# common-collector.net
KiCad netlist of a schematic drawn in EAGLE
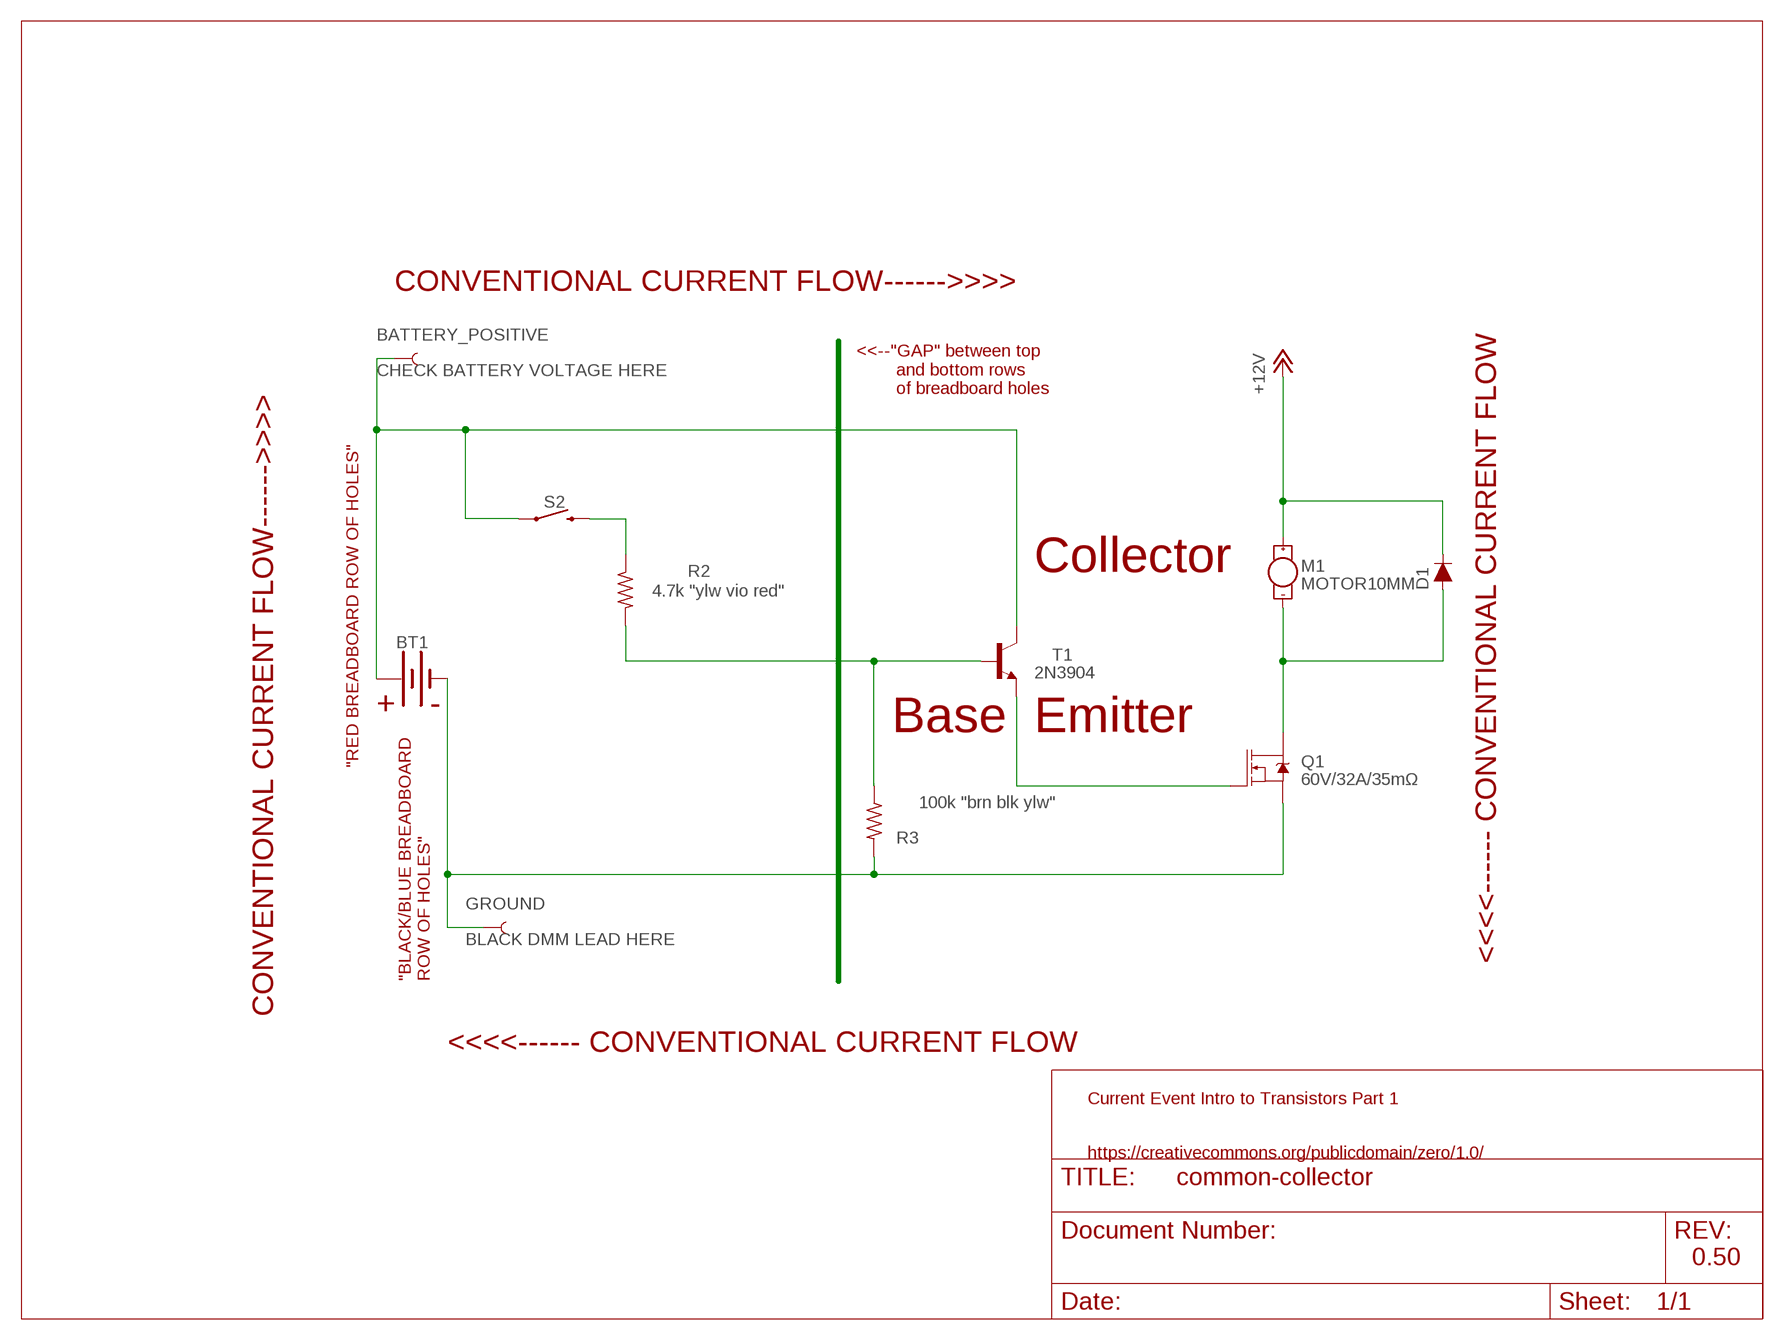
[diagram p0: schematic, sheet 1]

(export (version "E")
  (design (tool "Eeschema 10.0.6"))
  (components
    (comp (ref "BATTERY_POSITIVE")
      (value "CHECK BATTERY VOLTAGE HERE")
      (footprint "eagle-import:PAD.02X.02")
      (libsource (lib "eagle-import") (part "TEST-POINT2"))
    )
    (comp (ref "BT1")
      (value "BATTERY-AAA_KIT")
      (footprint "eagle-import:BATTERY-AAA-KIT")
      (libsource (lib "eagle-import") (part "BATTERY-AAA_KIT"))
    )
    (comp (ref "D1")
      (value "DIODE-1N4148")
      (footprint "eagle-import:DIODE-1N4148")
      (libsource (lib "eagle-import") (part "DIODE-1N4148"))
    )
    (comp (ref "GROUND")
      (value "BLACK DMM LEAD HERE")
      (footprint "eagle-import:PAD.02X.02")
      (libsource (lib "eagle-import") (part "TEST-POINT2"))
    )
    (comp (ref "M1")
      (value "MOTOR10MM")
      (footprint "eagle-import:VIBE-MOTOR-10MM")
      (libsource (lib "eagle-import") (part "MOTOR10MM"))
    )
    (comp (ref "Q1")
      (value "60V/32A/35mΩ")
      (footprint "eagle-import:TO220V")
      (libsource (lib "eagle-import") (part "MOSFET-NCH-FQP30N06L"))
    )
    (comp (ref "R2")
      (value "4.7k \"ylw vio red\"")
      (footprint "eagle-import:0309_12")
      (libsource (lib "eagle-import") (part "R-US_0309/12"))
    )
    (comp (ref "R3")
      (value "100k \"brn blk ylw\"")
      (footprint "eagle-import:0309_12")
      (libsource (lib "eagle-import") (part "R-US_0309/12"))
    )
    (comp (ref "S2")
      (value "MOMENTARY-SWITCH-SPST-PTH-6.0MM-KIT")
      (footprint "eagle-import:TACTILE_SWITCH_PTH_6.0MM_KIT")
      (libsource (lib "eagle-import") (part "MOMENTARY-SWITCH-SPST-PTH-6.0MM-KIT"))
    )
    (comp (ref "T1")
      (value "2N3904")
      (footprint "eagle-import:TO92")
      (libsource (lib "eagle-import") (part "2N3904"))
    )
  )
  (nets
    (net (code "1") (name "+12V") (class "Default")
      (node (ref "D1") (pin "C") (pinfunction "C_C") (pintype "passive"))
      (node (ref "M1") (pin "+") (pinfunction "+_+") (pintype "bidirectional"))
    )
    (net (code "2") (name "Net-(BATTERY_POSITIVE-1)") (class "Default")
      (node (ref "BATTERY_POSITIVE") (pin "P$1") (pinfunction "1_P$1") (pintype "bidirectional"))
      (node (ref "BT1") (pin "PWR@1") (pinfunction "+_PWR@1") (pintype "power_in"))
      (node (ref "S2") (pin "1") (pinfunction "1_1") (pintype "passive"))
      (node (ref "T1") (pin "1") (pinfunction "C_1") (pintype "passive"))
    )
    (net (code "3") (name "Net-(BT1--)") (class "Default")
      (node (ref "BT1") (pin "GND@1") (pinfunction "-_GND@1") (pintype "power_in"))
      (node (ref "GROUND") (pin "P$1") (pinfunction "1_P$1") (pintype "bidirectional"))
      (node (ref "Q1") (pin "3") (pinfunction "S_3") (pintype "bidirectional"))
      (node (ref "R3") (pin "2") (pinfunction "2_2") (pintype "passive"))
    )
    (net (code "4") (name "Net-(Q1-D)") (class "Default")
      (node (ref "D1") (pin "A") (pinfunction "A_A") (pintype "passive"))
      (node (ref "M1") (pin "-") (pinfunction "-_-") (pintype "bidirectional"))
      (node (ref "Q1") (pin "2") (pinfunction "D_2") (pintype "bidirectional"))
    )
    (net (code "5") (name "Net-(Q1-G)") (class "Default")
      (node (ref "Q1") (pin "1") (pinfunction "G_1") (pintype "bidirectional"))
      (node (ref "T1") (pin "3") (pinfunction "E_3") (pintype "passive"))
    )
    (net (code "6") (name "Net-(S2-2)") (class "Default")
      (node (ref "R2") (pin "1") (pinfunction "1_1") (pintype "passive"))
      (node (ref "S2") (pin "3") (pinfunction "2_3") (pintype "passive"))
    )
    (net (code "7") (name "Net-(T1-B)") (class "Default")
      (node (ref "R2") (pin "2") (pinfunction "2_2") (pintype "passive"))
      (node (ref "R3") (pin "1") (pinfunction "1_1") (pintype "passive"))
      (node (ref "T1") (pin "2") (pinfunction "B_2") (pintype "passive"))
    )
  )
)
